# LetYourBodyMove.net
KiCad netlist of a schematic drawn in EAGLE
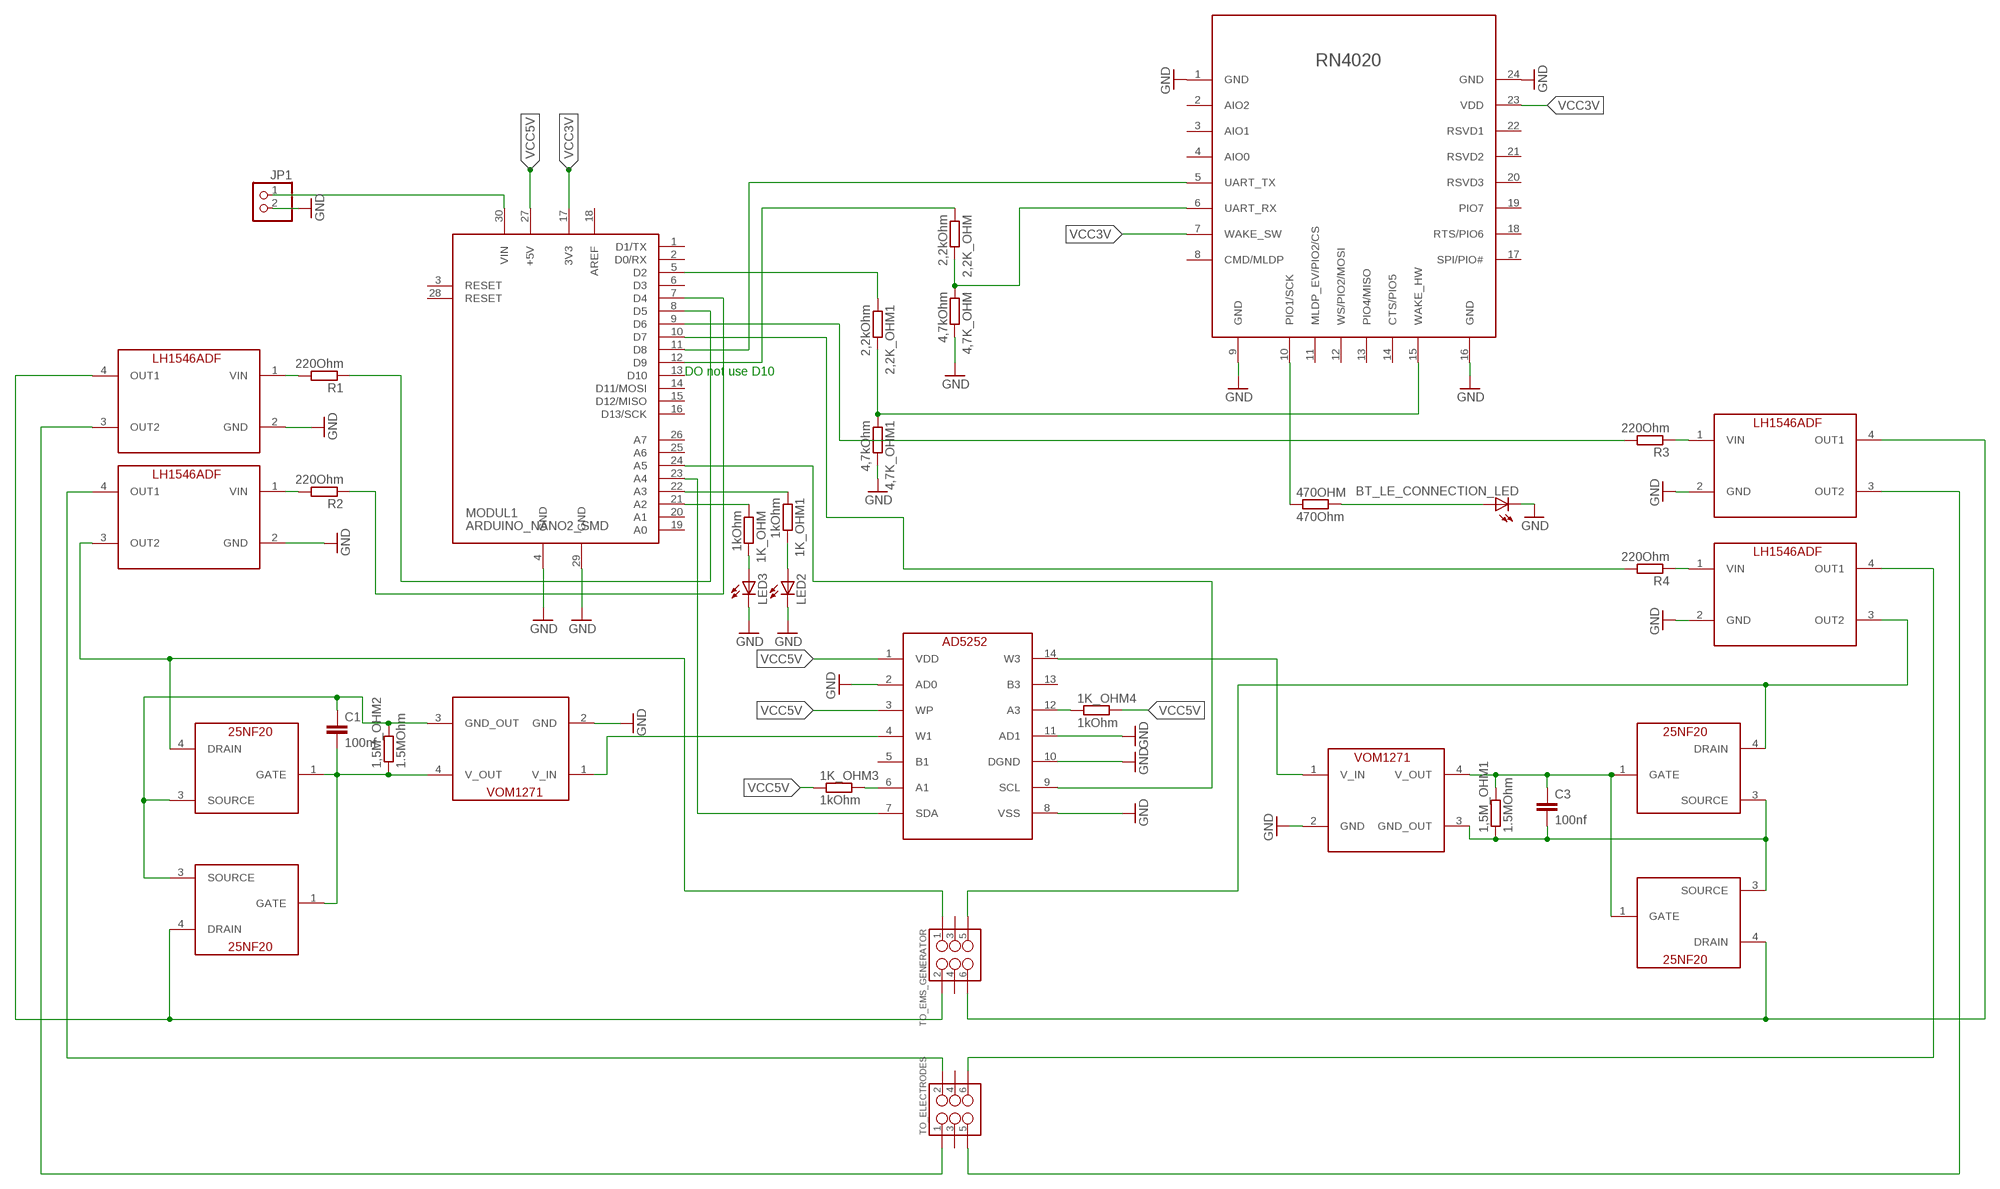
[diagram p0: schematic, sheet 1]

(export (version "E")
  (design (tool "Eeschema 10.0.6"))
  (components
    (comp (ref "1,5M_OHM1")
      (value "1.5MOhm")
      (footprint "eagle-import:R0805")
      (libsource (lib "eagle-import") (part "R-EU_R0805"))
    )
    (comp (ref "1,5M_OHM2")
      (value "1.5MOhm")
      (footprint "eagle-import:R0805")
      (libsource (lib "eagle-import") (part "R-EU_R0805"))
    )
    (comp (ref "1K_OHM")
      (value "1kOhm")
      (footprint "eagle-import:R0805")
      (libsource (lib "eagle-import") (part "R-EU_R0805"))
    )
    (comp (ref "1K_OHM1")
      (value "1kOhm")
      (footprint "eagle-import:R0805")
      (libsource (lib "eagle-import") (part "R-EU_R0805"))
    )
    (comp (ref "1K_OHM3")
      (value "1kOhm")
      (footprint "eagle-import:R0805")
      (libsource (lib "eagle-import") (part "R-EU_R0805"))
    )
    (comp (ref "1K_OHM4")
      (value "1kOhm")
      (footprint "eagle-import:R0805")
      (libsource (lib "eagle-import") (part "R-EU_R0805"))
    )
    (comp (ref "2,2K_OHM")
      (value "2,2kOhm")
      (footprint "eagle-import:R0805")
      (libsource (lib "eagle-import") (part "R-EU_R0805"))
    )
    (comp (ref "2,2K_OHM1")
      (value "2,2kOhm")
      (footprint "eagle-import:R0805")
      (libsource (lib "eagle-import") (part "R-EU_R0805"))
    )
    (comp (ref "4,7K_OHM")
      (value "4,7kOhm")
      (footprint "eagle-import:R0805")
      (libsource (lib "eagle-import") (part "R-EU_R0805"))
    )
    (comp (ref "4,7K_OHM1")
      (value "4,7kOhm")
      (footprint "eagle-import:R0805")
      (libsource (lib "eagle-import") (part "R-EU_R0805"))
    )
    (comp (ref "470OHM")
      (value "470Ohm")
      (footprint "eagle-import:R0805")
      (libsource (lib "eagle-import") (part "R-EU_R0805"))
    )
    (comp (ref "BT_LE_CONNECTION_LED")
      (value "LEDCHIPLED_0603")
      (footprint "eagle-import:CHIPLED_0603")
      (libsource (lib "eagle-import") (part "LEDCHIPLED_0603"))
    )
    (comp (ref "C1")
      (value "100nf")
      (footprint "eagle-import:0805")
      (libsource (lib "eagle-import") (part "CAP0805"))
    )
    (comp (ref "C3")
      (value "100nf")
      (footprint "eagle-import:0805")
      (libsource (lib "eagle-import") (part "CAP0805"))
    )
    (comp (ref "JP1")
      (value "PINHD-1X2")
      (footprint "eagle-import:1X02")
      (libsource (lib "eagle-import") (part "PINHD-1X2"))
    )
    (comp (ref "LED2")
      (value "LEDCHIPLED_0603")
      (footprint "eagle-import:CHIPLED_0603")
      (libsource (lib "eagle-import") (part "LEDCHIPLED_0603"))
    )
    (comp (ref "LED3")
      (value "LEDCHIPLED_0603")
      (footprint "eagle-import:CHIPLED_0603")
      (libsource (lib "eagle-import") (part "LEDCHIPLED_0603"))
    )
    (comp (ref "MODUL1")
      (value "ARDUINO_NANO2_SMD")
      (footprint "eagle-import:ARDUINO_NANO2_SMD")
      (libsource (lib "eagle-import") (part "ARDUINO_NANO2_SMD"))
    )
    (comp (ref "MOS01")
      (value "DEV")
      (footprint "eagle-import:PACK")
      (libsource (lib "eagle-import") (part "DEV"))
    )
    (comp (ref "MOS02")
      (value "DEV")
      (footprint "eagle-import:PACK")
      (libsource (lib "eagle-import") (part "DEV"))
    )
    (comp (ref "MOS03")
      (value "DEV")
      (footprint "eagle-import:PACK")
      (libsource (lib "eagle-import") (part "DEV"))
    )
    (comp (ref "MOS04")
      (value "DEV")
      (footprint "eagle-import:PACK")
      (libsource (lib "eagle-import") (part "DEV"))
    )
    (comp (ref "R1")
      (value "220Ohm")
      (footprint "eagle-import:R0805")
      (libsource (lib "eagle-import") (part "R-EU_R0805"))
    )
    (comp (ref "R2")
      (value "220Ohm")
      (footprint "eagle-import:R0805")
      (libsource (lib "eagle-import") (part "R-EU_R0805"))
    )
    (comp (ref "R3")
      (value "220Ohm")
      (footprint "eagle-import:R0805")
      (libsource (lib "eagle-import") (part "R-EU_R0805"))
    )
    (comp (ref "R4")
      (value "220Ohm")
      (footprint "eagle-import:R0805")
      (libsource (lib "eagle-import") (part "R-EU_R0805"))
    )
    (comp (ref "TO_ELECTRODES")
      (value "M03X2")
      (footprint "eagle-import:RIGHT_ANGLED_SHROUED_2X06_6PIN")
      (libsource (lib "eagle-import") (part "M03X2"))
    )
    (comp (ref "TO_EMS_GENERATOR")
      (value "M03X2")
      (footprint "eagle-import:RIGHT_ANGLED_SHROUED_2X06_6PIN")
      (libsource (lib "eagle-import") (part "M03X2"))
    )
    (comp (ref "U$5")
      (value "RN4020")
      (footprint "eagle-import:RN4020")
      (libsource (lib "eagle-import") (part "RN4020"))
    )
    (comp (ref "U$6")
      (value "AD5252")
      (footprint "eagle-import:TSSOP")
      (libsource (lib "eagle-import") (part "AD5252"))
    )
    (comp (ref "U$9")
      (value "VOM1271")
      (footprint "eagle-import:SOP04")
      (libsource (lib "eagle-import") (part "VOM1271"))
    )
    (comp (ref "U$10")
      (value "VOM1271")
      (footprint "eagle-import:SOP04")
      (libsource (lib "eagle-import") (part "VOM1271"))
    )
    (comp (ref "U$11")
      (value "LH1546ADF")
      (footprint "eagle-import:DIP04-SMD")
      (libsource (lib "eagle-import") (part "LH1546ADF"))
    )
    (comp (ref "U$12")
      (value "LH1546ADF")
      (footprint "eagle-import:DIP04-SMD")
      (libsource (lib "eagle-import") (part "LH1546ADF"))
    )
    (comp (ref "U$13")
      (value "LH1546ADF")
      (footprint "eagle-import:DIP04-SMD")
      (libsource (lib "eagle-import") (part "LH1546ADF"))
    )
    (comp (ref "U$14")
      (value "LH1546ADF")
      (footprint "eagle-import:DIP04-SMD")
      (libsource (lib "eagle-import") (part "LH1546ADF"))
    )
  )
  (nets
    (net (code "1") (name "/AREF") (class "Default")
      (node (ref "MODUL1") (pin "18") (pinfunction "AREF_18") (pintype "power_in"))
    )
    (net (code "2") (name "GND") (class "Default")
      (node (ref "4,7K_OHM") (pin "2") (pinfunction "2_2") (pintype "passive"))
      (node (ref "4,7K_OHM1") (pin "2") (pinfunction "2_2") (pintype "passive"))
      (node (ref "BT_LE_CONNECTION_LED") (pin "C") (pinfunction "C_C") (pintype "passive"))
      (node (ref "JP1") (pin "2") (pinfunction "2_2") (pintype "passive"))
      (node (ref "LED2") (pin "C") (pinfunction "C_C") (pintype "passive"))
      (node (ref "LED3") (pin "C") (pinfunction "C_C") (pintype "passive"))
      (node (ref "MODUL1") (pin "29") (pinfunction "GND_29") (pintype "power_in"))
      (node (ref "MODUL1") (pin "4") (pinfunction "GND_4") (pintype "power_in"))
      (node (ref "U$10") (pin "2") (pinfunction "GND_2") (pintype "input"))
      (node (ref "U$11") (pin "2") (pinfunction "GND_2") (pintype "bidirectional"))
      (node (ref "U$12") (pin "2") (pinfunction "GND_2") (pintype "bidirectional"))
      (node (ref "U$13") (pin "2") (pinfunction "GND_2") (pintype "bidirectional"))
      (node (ref "U$14") (pin "2") (pinfunction "GND_2") (pintype "bidirectional"))
      (node (ref "U$5") (pin "1") (pinfunction "GND_1") (pintype "power_in"))
      (node (ref "U$5") (pin "16") (pinfunction "GND_16") (pintype "power_in"))
      (node (ref "U$5") (pin "24") (pinfunction "GND_24") (pintype "power_in"))
      (node (ref "U$5") (pin "9") (pinfunction "GND_9") (pintype "power_in"))
      (node (ref "U$6") (pin "10") (pinfunction "DGND_10") (pintype "bidirectional"))
      (node (ref "U$6") (pin "11") (pinfunction "AD1_11") (pintype "bidirectional"))
      (node (ref "U$6") (pin "2") (pinfunction "AD0_2") (pintype "bidirectional"))
      (node (ref "U$6") (pin "8") (pinfunction "VSS_8") (pintype "bidirectional"))
      (node (ref "U$9") (pin "2") (pinfunction "GND_2") (pintype "input"))
    )
    (net (code "3") (name "Net-(1K_OHM-Pad2)") (class "Default")
      (node (ref "1K_OHM") (pin "2") (pinfunction "2_2") (pintype "passive"))
      (node (ref "LED3") (pin "A") (pinfunction "A_A") (pintype "passive"))
    )
    (net (code "4") (name "Net-(1K_OHM1-Pad2)") (class "Default")
      (node (ref "1K_OHM1") (pin "2") (pinfunction "2_2") (pintype "passive"))
      (node (ref "LED2") (pin "A") (pinfunction "A_A") (pintype "passive"))
    )
    (net (code "5") (name "Net-(470OHM-Pad2)") (class "Default")
      (node (ref "470OHM") (pin "2") (pinfunction "2_2") (pintype "passive"))
      (node (ref "BT_LE_CONNECTION_LED") (pin "A") (pinfunction "A_A") (pintype "passive"))
    )
    (net (code "6") (name "Net-(MODUL1-A2)") (class "Default")
      (node (ref "1K_OHM") (pin "1") (pinfunction "1_1") (pintype "passive"))
      (node (ref "MODUL1") (pin "21") (pinfunction "A2_21") (pintype "bidirectional"))
    )
    (net (code "7") (name "Net-(MODUL1-A3)") (class "Default")
      (node (ref "1K_OHM1") (pin "1") (pinfunction "1_1") (pintype "passive"))
      (node (ref "MODUL1") (pin "22") (pinfunction "A3_22") (pintype "bidirectional"))
    )
    (net (code "8") (name "Net-(MODUL1-A4)") (class "Default")
      (node (ref "MODUL1") (pin "23") (pinfunction "A4_23") (pintype "bidirectional"))
      (node (ref "U$6") (pin "7") (pinfunction "SDA_7") (pintype "bidirectional"))
    )
    (net (code "9") (name "Net-(MODUL1-A5)") (class "Default")
      (node (ref "MODUL1") (pin "24") (pinfunction "A5_24") (pintype "bidirectional"))
      (node (ref "U$6") (pin "9") (pinfunction "SCL_9") (pintype "bidirectional"))
    )
    (net (code "10") (name "Net-(MODUL1-D2)") (class "Default")
      (node (ref "2,2K_OHM1") (pin "1") (pinfunction "1_1") (pintype "passive"))
      (node (ref "MODUL1") (pin "5") (pinfunction "D2_5") (pintype "bidirectional"))
    )
    (net (code "11") (name "Net-(MODUL1-D4)") (class "Default")
      (node (ref "MODUL1") (pin "7") (pinfunction "D4_7") (pintype "bidirectional"))
      (node (ref "R2") (pin "1") (pinfunction "1_1") (pintype "passive"))
    )
    (net (code "12") (name "Net-(MODUL1-D5)") (class "Default")
      (node (ref "MODUL1") (pin "8") (pinfunction "D5_8") (pintype "bidirectional"))
      (node (ref "R1") (pin "1") (pinfunction "1_1") (pintype "passive"))
    )
    (net (code "13") (name "Net-(MODUL1-D6)") (class "Default")
      (node (ref "MODUL1") (pin "9") (pinfunction "D6_9") (pintype "bidirectional"))
      (node (ref "R3") (pin "2") (pinfunction "2_2") (pintype "passive"))
    )
    (net (code "14") (name "Net-(MODUL1-D7)") (class "Default")
      (node (ref "MODUL1") (pin "10") (pinfunction "D7_10") (pintype "bidirectional"))
      (node (ref "R4") (pin "2") (pinfunction "2_2") (pintype "passive"))
    )
    (net (code "15") (name "Net-(MODUL1-D8)") (class "Default")
      (node (ref "MODUL1") (pin "11") (pinfunction "D8_11") (pintype "bidirectional"))
      (node (ref "U$5") (pin "5") (pinfunction "UART_TX_5") (pintype "bidirectional"))
    )
    (net (code "16") (name "Net-(MODUL1-D9)") (class "Default")
      (node (ref "2,2K_OHM") (pin "1") (pinfunction "1_1") (pintype "passive"))
      (node (ref "MODUL1") (pin "12") (pinfunction "D9_12") (pintype "bidirectional"))
    )
    (net (code "17") (name "Net-(MODUL1-VIN)") (class "Default")
      (node (ref "JP1") (pin "1") (pinfunction "1_1") (pintype "passive"))
      (node (ref "MODUL1") (pin "30") (pinfunction "VIN_30") (pintype "power_in"))
    )
    (net (code "18") (name "Net-(MOS01-DRAIN)") (class "Default")
      (node (ref "MOS01") (pin "4") (pinfunction "DRAIN_4") (pintype "bidirectional"))
      (node (ref "TO_EMS_GENERATOR") (pin "1") (pinfunction "1_1") (pintype "bidirectional"))
      (node (ref "U$12") (pin "3") (pinfunction "OUT2_3") (pintype "bidirectional"))
    )
    (net (code "19") (name "Net-(MOS01-GATE)") (class "Default")
      (node (ref "1,5M_OHM2") (pin "1") (pinfunction "1_1") (pintype "passive"))
      (node (ref "C1") (pin "2") (pinfunction "2_2") (pintype "passive"))
      (node (ref "MOS01") (pin "1") (pinfunction "GATE_1") (pintype "input"))
      (node (ref "MOS02") (pin "1") (pinfunction "GATE_1") (pintype "input"))
      (node (ref "U$9") (pin "4") (pinfunction "V_OUT_4") (pintype "output"))
    )
    (net (code "20") (name "Net-(MOS01-SOURCE)") (class "Default")
      (node (ref "1,5M_OHM2") (pin "2") (pinfunction "2_2") (pintype "passive"))
      (node (ref "C1") (pin "1") (pinfunction "1_1") (pintype "passive"))
      (node (ref "MOS01") (pin "3") (pinfunction "SOURCE_3") (pintype "bidirectional"))
      (node (ref "MOS02") (pin "3") (pinfunction "SOURCE_3") (pintype "bidirectional"))
      (node (ref "U$9") (pin "3") (pinfunction "GND_OUT_3") (pintype "output"))
    )
    (net (code "21") (name "Net-(MOS02-DRAIN)") (class "Default")
      (node (ref "MOS02") (pin "4") (pinfunction "DRAIN_4") (pintype "bidirectional"))
      (node (ref "TO_EMS_GENERATOR") (pin "2") (pinfunction "2_2") (pintype "bidirectional"))
      (node (ref "U$11") (pin "4") (pinfunction "OUT1_4") (pintype "bidirectional"))
    )
    (net (code "22") (name "Net-(MOS03-DRAIN)") (class "Default")
      (node (ref "MOS03") (pin "4") (pinfunction "DRAIN_4") (pintype "bidirectional"))
      (node (ref "TO_EMS_GENERATOR") (pin "5") (pinfunction "5_5") (pintype "bidirectional"))
      (node (ref "U$14") (pin "3") (pinfunction "OUT2_3") (pintype "bidirectional"))
    )
    (net (code "23") (name "Net-(MOS03-GATE)") (class "Default")
      (node (ref "1,5M_OHM1") (pin "2") (pinfunction "2_2") (pintype "passive"))
      (node (ref "C3") (pin "1") (pinfunction "1_1") (pintype "passive"))
      (node (ref "MOS03") (pin "1") (pinfunction "GATE_1") (pintype "input"))
      (node (ref "MOS04") (pin "1") (pinfunction "GATE_1") (pintype "input"))
      (node (ref "U$10") (pin "4") (pinfunction "V_OUT_4") (pintype "output"))
    )
    (net (code "24") (name "Net-(MOS03-SOURCE)") (class "Default")
      (node (ref "1,5M_OHM1") (pin "1") (pinfunction "1_1") (pintype "passive"))
      (node (ref "C3") (pin "2") (pinfunction "2_2") (pintype "passive"))
      (node (ref "MOS03") (pin "3") (pinfunction "SOURCE_3") (pintype "bidirectional"))
      (node (ref "MOS04") (pin "3") (pinfunction "SOURCE_3") (pintype "bidirectional"))
      (node (ref "U$10") (pin "3") (pinfunction "GND_OUT_3") (pintype "output"))
    )
    (net (code "25") (name "Net-(MOS04-DRAIN)") (class "Default")
      (node (ref "MOS04") (pin "4") (pinfunction "DRAIN_4") (pintype "bidirectional"))
      (node (ref "TO_EMS_GENERATOR") (pin "6") (pinfunction "6_6") (pintype "bidirectional"))
      (node (ref "U$13") (pin "4") (pinfunction "OUT1_4") (pintype "bidirectional"))
    )
    (net (code "26") (name "Net-(U$5-PIO1{slash}SCK)") (class "Default")
      (node (ref "470OHM") (pin "1") (pinfunction "1_1") (pintype "passive"))
      (node (ref "U$5") (pin "10") (pinfunction "PIO1/SCK_10") (pintype "bidirectional"))
    )
    (net (code "27") (name "Net-(U$5-UART_RX)") (class "Default")
      (node (ref "2,2K_OHM") (pin "2") (pinfunction "2_2") (pintype "passive"))
      (node (ref "4,7K_OHM") (pin "1") (pinfunction "1_1") (pintype "passive"))
      (node (ref "U$5") (pin "6") (pinfunction "UART_RX_6") (pintype "bidirectional"))
    )
    (net (code "28") (name "Net-(U$5-WAKE_HW)") (class "Default")
      (node (ref "2,2K_OHM1") (pin "2") (pinfunction "2_2") (pintype "passive"))
      (node (ref "4,7K_OHM1") (pin "1") (pinfunction "1_1") (pintype "passive"))
      (node (ref "U$5") (pin "15") (pinfunction "WAKE_HW_15") (pintype "bidirectional"))
    )
    (net (code "29") (name "Net-(U$6-A1)") (class "Default")
      (node (ref "1K_OHM3") (pin "2") (pinfunction "2_2") (pintype "passive"))
      (node (ref "U$6") (pin "6") (pinfunction "A1_6") (pintype "bidirectional"))
    )
    (net (code "30") (name "Net-(U$6-A3)") (class "Default")
      (node (ref "1K_OHM4") (pin "1") (pinfunction "1_1") (pintype "passive"))
      (node (ref "U$6") (pin "12") (pinfunction "A3_12") (pintype "bidirectional"))
    )
    (net (code "31") (name "Net-(U$6-W1)") (class "Default")
      (node (ref "U$6") (pin "4") (pinfunction "W1_4") (pintype "bidirectional"))
      (node (ref "U$9") (pin "1") (pinfunction "V_IN_1") (pintype "input"))
    )
    (net (code "32") (name "Net-(U$10-V_IN)") (class "Default")
      (node (ref "U$10") (pin "1") (pinfunction "V_IN_1") (pintype "input"))
      (node (ref "U$6") (pin "14") (pinfunction "W3_14") (pintype "bidirectional"))
    )
    (net (code "33") (name "Net-(U$11-OUT2)") (class "Default")
      (node (ref "TO_ELECTRODES") (pin "1") (pinfunction "1_1") (pintype "bidirectional"))
      (node (ref "U$11") (pin "3") (pinfunction "OUT2_3") (pintype "bidirectional"))
    )
    (net (code "34") (name "Net-(U$11-VIN)") (class "Default")
      (node (ref "R1") (pin "2") (pinfunction "2_2") (pintype "passive"))
      (node (ref "U$11") (pin "1") (pinfunction "VIN_1") (pintype "bidirectional"))
    )
    (net (code "35") (name "Net-(U$12-OUT1)") (class "Default")
      (node (ref "TO_ELECTRODES") (pin "2") (pinfunction "2_2") (pintype "bidirectional"))
      (node (ref "U$12") (pin "4") (pinfunction "OUT1_4") (pintype "bidirectional"))
    )
    (net (code "36") (name "Net-(U$12-VIN)") (class "Default")
      (node (ref "R2") (pin "2") (pinfunction "2_2") (pintype "passive"))
      (node (ref "U$12") (pin "1") (pinfunction "VIN_1") (pintype "bidirectional"))
    )
    (net (code "37") (name "Net-(U$13-OUT2)") (class "Default")
      (node (ref "TO_ELECTRODES") (pin "5") (pinfunction "5_5") (pintype "bidirectional"))
      (node (ref "U$13") (pin "3") (pinfunction "OUT2_3") (pintype "bidirectional"))
    )
    (net (code "38") (name "Net-(U$13-VIN)") (class "Default")
      (node (ref "R3") (pin "1") (pinfunction "1_1") (pintype "passive"))
      (node (ref "U$13") (pin "1") (pinfunction "VIN_1") (pintype "bidirectional"))
    )
    (net (code "39") (name "Net-(U$14-OUT1)") (class "Default")
      (node (ref "TO_ELECTRODES") (pin "6") (pinfunction "6_6") (pintype "bidirectional"))
      (node (ref "U$14") (pin "4") (pinfunction "OUT1_4") (pintype "bidirectional"))
    )
    (net (code "40") (name "Net-(U$14-VIN)") (class "Default")
      (node (ref "R4") (pin "1") (pinfunction "1_1") (pintype "passive"))
      (node (ref "U$14") (pin "1") (pinfunction "VIN_1") (pintype "bidirectional"))
    )
    (net (code "41") (name "VCC3V") (class "Default")
      (node (ref "MODUL1") (pin "17") (pinfunction "3V3_17") (pintype "power_in"))
      (node (ref "U$5") (pin "23") (pinfunction "VDD_23") (pintype "power_in"))
      (node (ref "U$5") (pin "7") (pinfunction "WAKE_SW_7") (pintype "bidirectional"))
    )
    (net (code "42") (name "VCC5V") (class "Default")
      (node (ref "1K_OHM3") (pin "1") (pinfunction "1_1") (pintype "passive"))
      (node (ref "1K_OHM4") (pin "2") (pinfunction "2_2") (pintype "passive"))
      (node (ref "MODUL1") (pin "27") (pinfunction "+5V_27") (pintype "power_in"))
      (node (ref "U$6") (pin "1") (pinfunction "VDD_1") (pintype "bidirectional"))
      (node (ref "U$6") (pin "3") (pinfunction "WP_3") (pintype "bidirectional"))
    )
    (net (code "43") (name "unconnected-(MODUL1-A0-Pad19)") (class "Default")
      (node (ref "MODUL1") (pin "19") (pinfunction "A0_19") (pintype "bidirectional"))
    )
    (net (code "44") (name "unconnected-(MODUL1-A1-Pad20)") (class "Default")
      (node (ref "MODUL1") (pin "20") (pinfunction "A1_20") (pintype "bidirectional"))
    )
    (net (code "45") (name "unconnected-(MODUL1-A6-Pad25)") (class "Default")
      (node (ref "MODUL1") (pin "25") (pinfunction "A6_25") (pintype "bidirectional"))
    )
    (net (code "46") (name "unconnected-(MODUL1-A7-Pad26)") (class "Default")
      (node (ref "MODUL1") (pin "26") (pinfunction "A7_26") (pintype "bidirectional"))
    )
    (net (code "47") (name "unconnected-(MODUL1-D0{slash}RX-Pad2)") (class "Default")
      (node (ref "MODUL1") (pin "2") (pinfunction "D0/RX_2") (pintype "bidirectional"))
    )
    (net (code "48") (name "unconnected-(MODUL1-D1{slash}TX-Pad1)") (class "Default")
      (node (ref "MODUL1") (pin "1") (pinfunction "D1/TX_1") (pintype "bidirectional"))
    )
    (net (code "49") (name "unconnected-(MODUL1-D3-Pad6)") (class "Default")
      (node (ref "MODUL1") (pin "6") (pinfunction "D3_6") (pintype "bidirectional"))
    )
    (net (code "50") (name "unconnected-(MODUL1-D10-Pad13)") (class "Default")
      (node (ref "MODUL1") (pin "13") (pinfunction "D10_13") (pintype "bidirectional"))
    )
    (net (code "51") (name "unconnected-(MODUL1-D11{slash}MOSI-Pad14)") (class "Default")
      (node (ref "MODUL1") (pin "14") (pinfunction "D11/MOSI_14") (pintype "bidirectional"))
    )
    (net (code "52") (name "unconnected-(MODUL1-D12{slash}MISO-Pad15)") (class "Default")
      (node (ref "MODUL1") (pin "15") (pinfunction "D12/MISO_15") (pintype "bidirectional"))
    )
    (net (code "53") (name "unconnected-(MODUL1-D13{slash}SCK-Pad16)") (class "Default")
      (node (ref "MODUL1") (pin "16") (pinfunction "D13/SCK_16") (pintype "bidirectional"))
    )
    (net (code "54") (name "unconnected-(MODUL1-RESET-Pad3)") (class "Default")
      (node (ref "MODUL1") (pin "3") (pinfunction "RESET_3") (pintype "bidirectional"))
    )
    (net (code "55") (name "unconnected-(MODUL1-RESET-Pad28)") (class "Default")
      (node (ref "MODUL1") (pin "28") (pinfunction "RESET_28") (pintype "bidirectional"))
    )
    (net (code "56") (name "unconnected-(TO_ELECTRODES-Pad3)") (class "Default")
      (node (ref "TO_ELECTRODES") (pin "3") (pinfunction "3_3") (pintype "bidirectional"))
    )
    (net (code "57") (name "unconnected-(TO_ELECTRODES-Pad4)") (class "Default")
      (node (ref "TO_ELECTRODES") (pin "4") (pinfunction "4_4") (pintype "bidirectional"))
    )
    (net (code "58") (name "unconnected-(TO_EMS_GENERATOR-Pad3)") (class "Default")
      (node (ref "TO_EMS_GENERATOR") (pin "3") (pinfunction "3_3") (pintype "bidirectional"))
    )
    (net (code "59") (name "unconnected-(TO_EMS_GENERATOR-Pad4)") (class "Default")
      (node (ref "TO_EMS_GENERATOR") (pin "4") (pinfunction "4_4") (pintype "bidirectional"))
    )
    (net (code "60") (name "unconnected-(U$5-AIO0-Pad4)") (class "Default")
      (node (ref "U$5") (pin "4") (pinfunction "AIO0_4") (pintype "bidirectional"))
    )
    (net (code "61") (name "unconnected-(U$5-AIO1-Pad3)") (class "Default")
      (node (ref "U$5") (pin "3") (pinfunction "AIO1_3") (pintype "bidirectional"))
    )
    (net (code "62") (name "unconnected-(U$5-AIO2-Pad2)") (class "Default")
      (node (ref "U$5") (pin "2") (pinfunction "AIO2_2") (pintype "bidirectional"))
    )
    (net (code "63") (name "unconnected-(U$5-CMD{slash}MLDP-Pad8)") (class "Default")
      (node (ref "U$5") (pin "8") (pinfunction "CMD/MLDP_8") (pintype "bidirectional"))
    )
    (net (code "64") (name "unconnected-(U$5-CTS{slash}PIO5-Pad14)") (class "Default")
      (node (ref "U$5") (pin "14") (pinfunction "CTS/PIO5_14") (pintype "bidirectional"))
    )
    (net (code "65") (name "unconnected-(U$5-MLDP_EV{slash}PIO2{slash}CS-Pad11)") (class "Default")
      (node (ref "U$5") (pin "11") (pinfunction "MLDP_EV/PIO2/CS_11") (pintype "bidirectional"))
    )
    (net (code "66") (name "unconnected-(U$5-PIO4{slash}MISO-Pad13)") (class "Default")
      (node (ref "U$5") (pin "13") (pinfunction "PIO4/MISO_13") (pintype "bidirectional"))
    )
    (net (code "67") (name "unconnected-(U$5-PIO7-Pad19)") (class "Default")
      (node (ref "U$5") (pin "19") (pinfunction "PIO7_19") (pintype "bidirectional"))
    )
    (net (code "68") (name "unconnected-(U$5-RSVD1-Pad22)") (class "Default")
      (node (ref "U$5") (pin "22") (pinfunction "RSVD1_22") (pintype "bidirectional"))
    )
    (net (code "69") (name "unconnected-(U$5-RSVD2-Pad21)") (class "Default")
      (node (ref "U$5") (pin "21") (pinfunction "RSVD2_21") (pintype "bidirectional"))
    )
    (net (code "70") (name "unconnected-(U$5-RSVD3-Pad20)") (class "Default")
      (node (ref "U$5") (pin "20") (pinfunction "RSVD3_20") (pintype "bidirectional"))
    )
    (net (code "71") (name "unconnected-(U$5-RTS{slash}PIO6-Pad18)") (class "Default")
      (node (ref "U$5") (pin "18") (pinfunction "RTS/PIO6_18") (pintype "bidirectional"))
    )
    (net (code "72") (name "unconnected-(U$5-SPI{slash}PIO#-Pad17)") (class "Default")
      (node (ref "U$5") (pin "17") (pinfunction "SPI/PIO#_17") (pintype "bidirectional"))
    )
    (net (code "73") (name "unconnected-(U$5-WS{slash}PIO2{slash}MOSI-Pad12)") (class "Default")
      (node (ref "U$5") (pin "12") (pinfunction "WS/PIO2/MOSI_12") (pintype "bidirectional"))
    )
    (net (code "74") (name "unconnected-(U$6-B1-Pad5)") (class "Default")
      (node (ref "U$6") (pin "5") (pinfunction "B1_5") (pintype "bidirectional"))
    )
    (net (code "75") (name "unconnected-(U$6-B3-Pad13)") (class "Default")
      (node (ref "U$6") (pin "13") (pinfunction "B3_13") (pintype "bidirectional"))
    )
  )
)
